# PLD_SunSref-Interface.net
KiCad netlist of a schematic drawn in Altium Designer
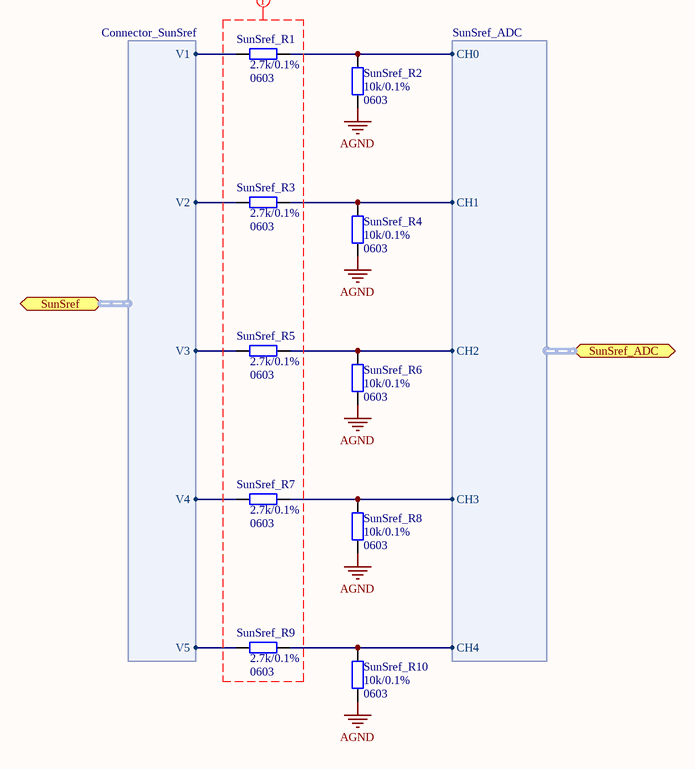
[diagram p0: PLD_SunSref-Interface.SchDoc]

(export (version "E")
  (design (tool "Eeschema 10.0.6"))
  (components
    (comp (ref "SunSref_R1")
      (value "2.7k/0.1%")
      (footprint "SMD_Resistor_0603")
      (fields (field (name "PACKAGE") "0603"))
      (libsource (lib "") (part "Res_1"))
    )
    (comp (ref "SunSref_R2")
      (value "10k/0.1%")
      (footprint "SMD_Resistor_0603")
      (fields (field (name "PACKAGE") "0603"))
      (libsource (lib "resistors") (part "Res"))
    )
    (comp (ref "SunSref_R3")
      (value "2.7k/0.1%")
      (footprint "SMD_Resistor_0603")
      (fields (field (name "PACKAGE") "0603"))
      (libsource (lib "") (part "Res_1"))
    )
    (comp (ref "SunSref_R4")
      (value "10k/0.1%")
      (footprint "SMD_Resistor_0603")
      (fields (field (name "PACKAGE") "0603"))
      (libsource (lib "resistors") (part "Res"))
    )
    (comp (ref "SunSref_R5")
      (value "2.7k/0.1%")
      (footprint "SMD_Resistor_0603")
      (fields (field (name "PACKAGE") "0603"))
      (libsource (lib "") (part "Res_1"))
    )
    (comp (ref "SunSref_R6")
      (value "10k/0.1%")
      (footprint "SMD_Resistor_0603")
      (fields (field (name "PACKAGE") "0603"))
      (libsource (lib "resistors") (part "Res"))
    )
    (comp (ref "SunSref_R7")
      (value "2.7k/0.1%")
      (footprint "SMD_Resistor_0603")
      (fields (field (name "PACKAGE") "0603"))
      (libsource (lib "") (part "Res_1"))
    )
    (comp (ref "SunSref_R8")
      (value "10k/0.1%")
      (footprint "SMD_Resistor_0603")
      (fields (field (name "PACKAGE") "0603"))
      (libsource (lib "resistors") (part "Res"))
    )
    (comp (ref "SunSref_R9")
      (value "2.7k/0.1%")
      (footprint "SMD_Resistor_0603")
      (fields (field (name "PACKAGE") "0603"))
      (libsource (lib "") (part "Res_1"))
    )
    (comp (ref "SunSref_R10")
      (value "10k/0.1%")
      (footprint "SMD_Resistor_0603")
      (fields (field (name "PACKAGE") "0603"))
      (libsource (lib "resistors") (part "Res"))
    )
  )
  (nets
    (net (code "3") (name "/CH0") (class "Default")
      (node (ref "SunSref_R1") (pin "2") (pinfunction "2_2") (pintype "passive"))
      (node (ref "SunSref_R2") (pin "2") (pinfunction "2_2") (pintype "passive"))
    )
    (net (code "4") (name "/CH1") (class "Default")
      (node (ref "SunSref_R3") (pin "2") (pinfunction "2_2") (pintype "passive"))
      (node (ref "SunSref_R4") (pin "2") (pinfunction "2_2") (pintype "passive"))
    )
    (net (code "5") (name "/CH2") (class "Default")
      (node (ref "SunSref_R5") (pin "2") (pinfunction "2_2") (pintype "passive"))
      (node (ref "SunSref_R6") (pin "2") (pinfunction "2_2") (pintype "passive"))
    )
    (net (code "6") (name "/CH3") (class "Default")
      (node (ref "SunSref_R7") (pin "2") (pinfunction "2_2") (pintype "passive"))
      (node (ref "SunSref_R8") (pin "2") (pinfunction "2_2") (pintype "passive"))
    )
    (net (code "7") (name "/CH4") (class "Default")
      (node (ref "SunSref_R10") (pin "2") (pinfunction "2_2") (pintype "passive"))
      (node (ref "SunSref_R9") (pin "2") (pinfunction "2_2") (pintype "passive"))
    )
    (net (code "8") (name "/V1") (class "Default")
      (node (ref "SunSref_R1") (pin "1") (pinfunction "1_1") (pintype "passive"))
    )
    (net (code "9") (name "/V2") (class "Default")
      (node (ref "SunSref_R3") (pin "1") (pinfunction "1_1") (pintype "passive"))
    )
    (net (code "10") (name "/V3") (class "Default")
      (node (ref "SunSref_R5") (pin "1") (pinfunction "1_1") (pintype "passive"))
    )
    (net (code "11") (name "/V4") (class "Default")
      (node (ref "SunSref_R7") (pin "1") (pinfunction "1_1") (pintype "passive"))
    )
    (net (code "12") (name "/V5") (class "Default")
      (node (ref "SunSref_R9") (pin "1") (pinfunction "1_1") (pintype "passive"))
    )
    (net (code "15") (name "AGND") (class "Default")
      (node (ref "SunSref_R10") (pin "1") (pinfunction "1_1") (pintype "passive"))
      (node (ref "SunSref_R2") (pin "1") (pinfunction "1_1") (pintype "passive"))
      (node (ref "SunSref_R4") (pin "1") (pinfunction "1_1") (pintype "passive"))
      (node (ref "SunSref_R6") (pin "1") (pinfunction "1_1") (pintype "passive"))
      (node (ref "SunSref_R8") (pin "1") (pinfunction "1_1") (pintype "passive"))
    )
  )
)
